# NBP3_Altera_MAX7000_MAX3000_PLCC_Rev1_00.net
KiCad netlist of a schematic drawn in Altium Designer
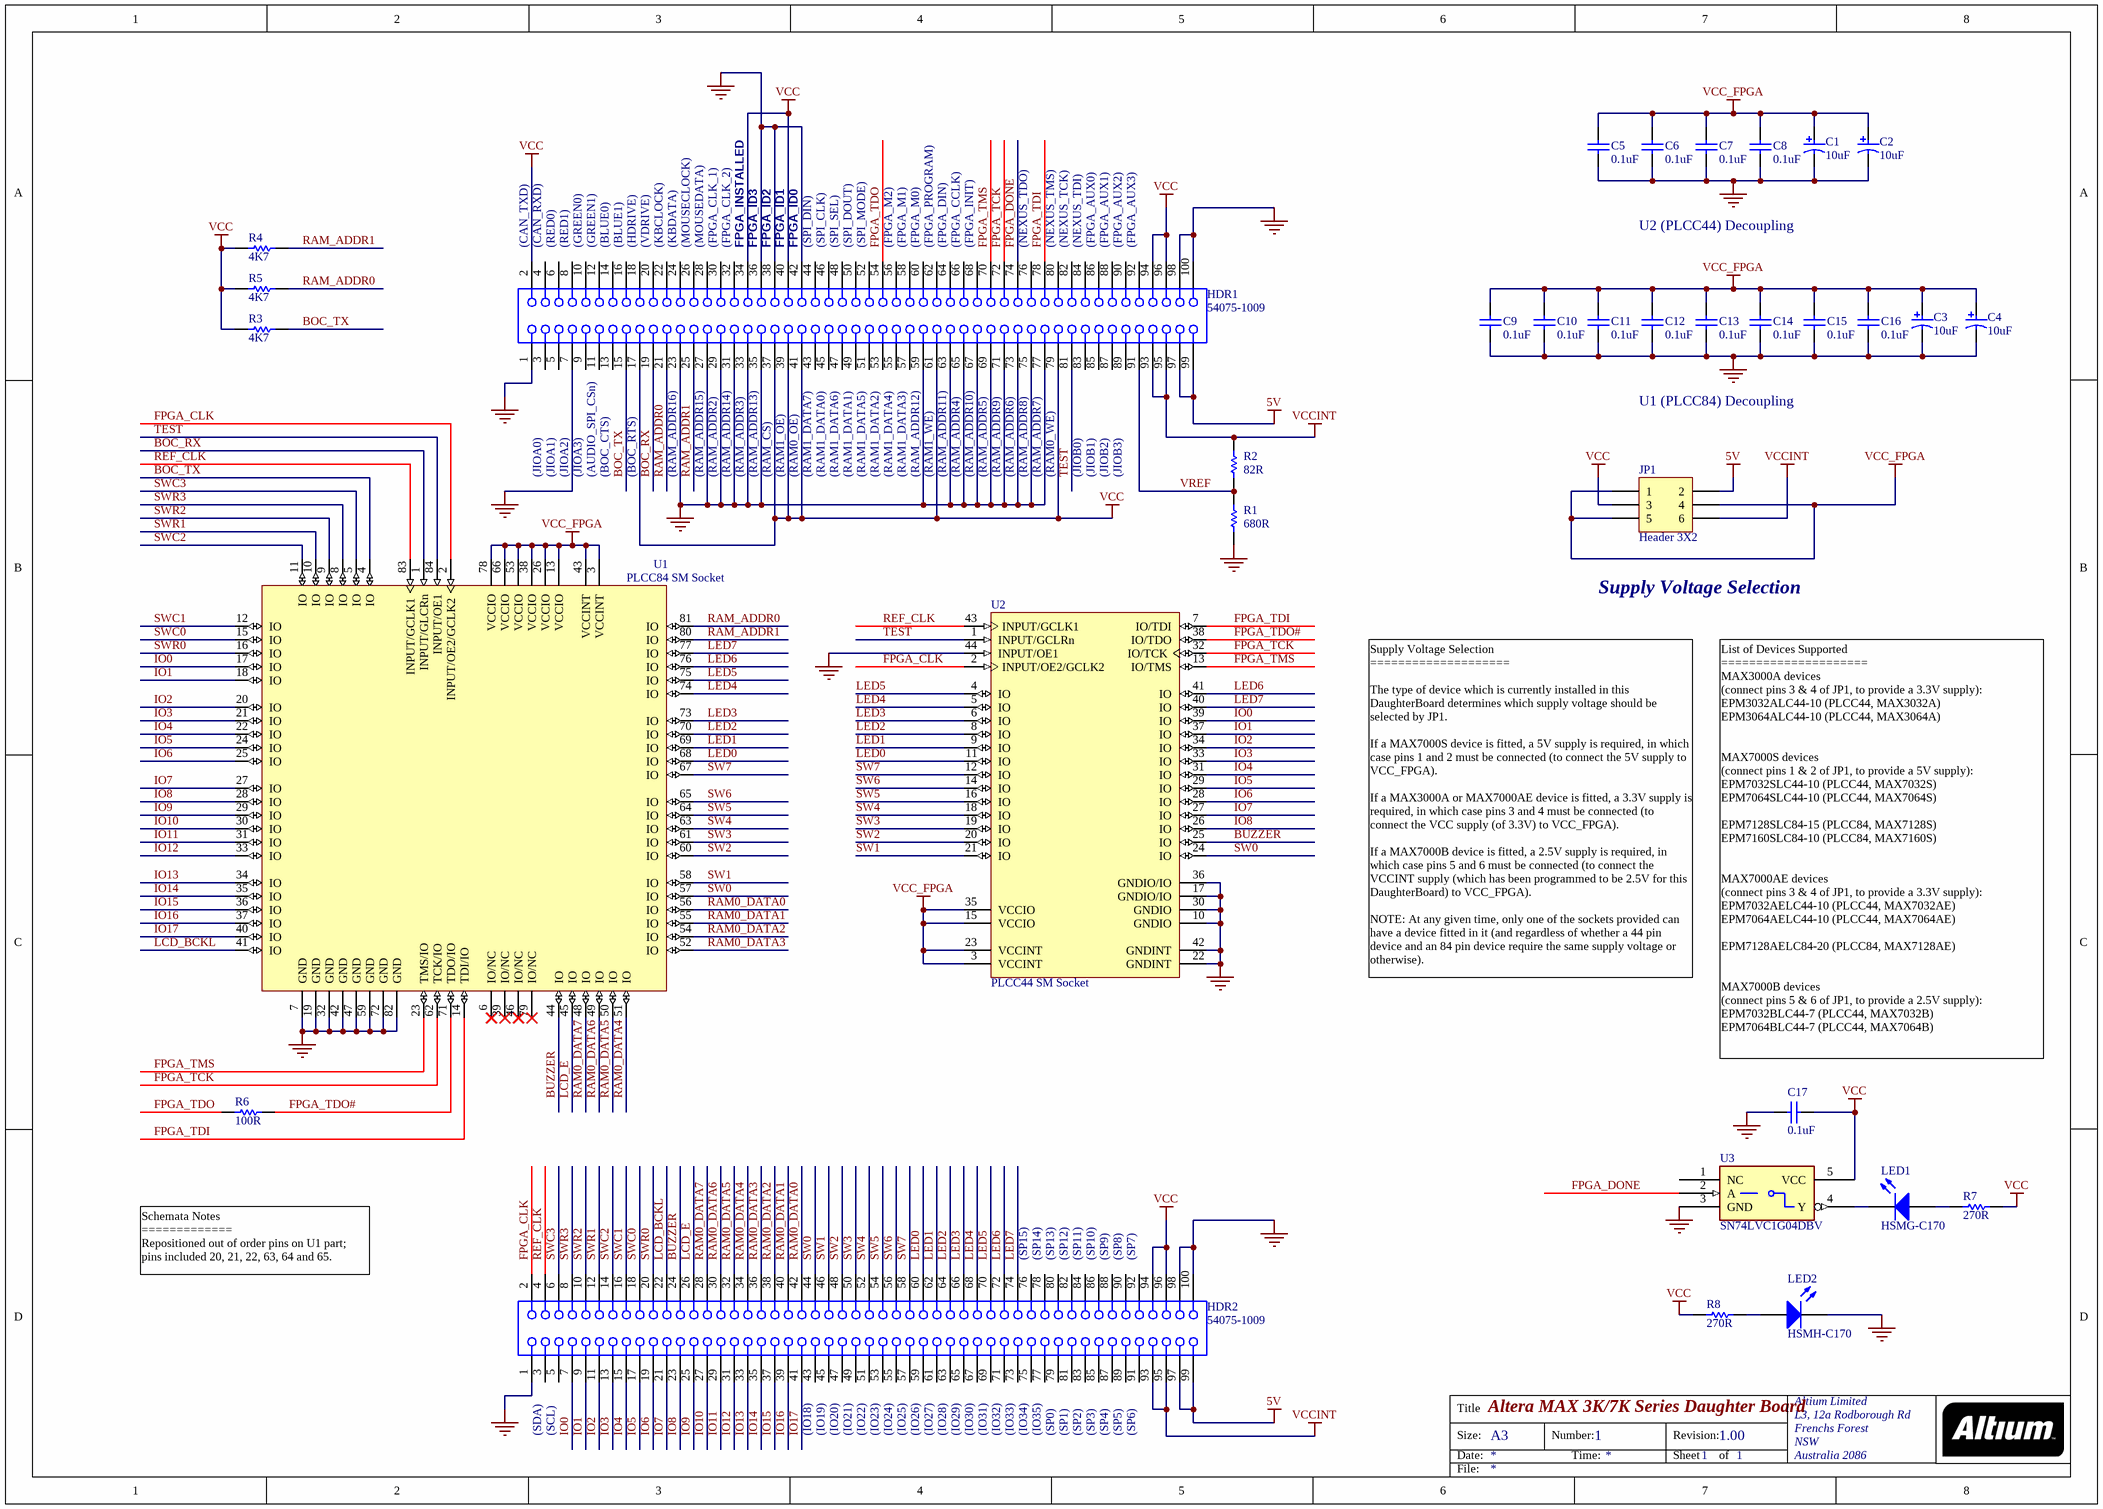
[diagram p0: NBP3 Altera MAX7000 MAX3000 PLCC Rev1.00.SchDoc]

(export (version "E")
  (design (tool "Eeschema 10.0.6"))
  (components
    (comp (ref "C1")
      (value "10uF")
      (footprint "MCCT-B")
      (description "Polar Capacitor")
      (libsource (lib "PassiveSMD") (part "CAP_POLAR"))
    )
    (comp (ref "C2")
      (value "10uF")
      (footprint "MCCT-B")
      (description "Polar Capacitor")
      (libsource (lib "PassiveSMD") (part "CAP_POLAR"))
    )
    (comp (ref "C3")
      (value "10uF")
      (footprint "MCCT-B")
      (description "Polar Capacitor")
      (libsource (lib "PassiveSMD") (part "CAP_POLAR"))
    )
    (comp (ref "C4")
      (value "10uF")
      (footprint "MCCT-B")
      (description "Polar Capacitor")
      (libsource (lib "PassiveSMD") (part "CAP_POLAR"))
    )
    (comp (ref "C5")
      (value "0.1uF")
      (footprint "CC2012-0805")
      (description "Capacitor")
      (libsource (lib "PassiveSMD") (part "CAP"))
    )
    (comp (ref "C6")
      (value "0.1uF")
      (footprint "CC2012-0805")
      (description "Capacitor")
      (libsource (lib "PassiveSMD") (part "CAP"))
    )
    (comp (ref "C7")
      (value "0.1uF")
      (footprint "CC2012-0805")
      (description "Capacitor")
      (libsource (lib "PassiveSMD") (part "CAP"))
    )
    (comp (ref "C8")
      (value "0.1uF")
      (footprint "CC2012-0805")
      (description "Capacitor")
      (libsource (lib "PassiveSMD") (part "CAP"))
    )
    (comp (ref "C9")
      (value "0.1uF")
      (footprint "CC2012-0805")
      (description "Capacitor")
      (libsource (lib "PassiveSMD") (part "CAP"))
    )
    (comp (ref "C10")
      (value "0.1uF")
      (footprint "CC2012-0805")
      (description "Capacitor")
      (libsource (lib "PassiveSMD") (part "CAP"))
    )
    (comp (ref "C11")
      (value "0.1uF")
      (footprint "CC2012-0805")
      (description "Capacitor")
      (libsource (lib "PassiveSMD") (part "CAP"))
    )
    (comp (ref "C12")
      (value "0.1uF")
      (footprint "CC2012-0805")
      (description "Capacitor")
      (libsource (lib "PassiveSMD") (part "CAP"))
    )
    (comp (ref "C13")
      (value "0.1uF")
      (footprint "CC2012-0805")
      (description "Capacitor")
      (libsource (lib "PassiveSMD") (part "CAP"))
    )
    (comp (ref "C14")
      (value "0.1uF")
      (footprint "CC2012-0805")
      (description "Capacitor")
      (libsource (lib "PassiveSMD") (part "CAP"))
    )
    (comp (ref "C15")
      (value "0.1uF")
      (footprint "CC2012-0805")
      (description "Capacitor")
      (libsource (lib "PassiveSMD") (part "CAP"))
    )
    (comp (ref "C16")
      (value "0.1uF")
      (footprint "CC2012-0805")
      (description "Capacitor")
      (libsource (lib "PassiveSMD") (part "CAP"))
    )
    (comp (ref "C17")
      (value "0.1uF")
      (footprint "CC2012-0805")
      (description "Capacitor")
      (libsource (lib "PassiveSMD") (part "CAP"))
    )
    (comp (ref "HDR1")
      (value "54075-1009")
      (footprint "54075")
      (fields
        (field (name "MANUFACTURER") "Molex")
        (field (name "VOLTAGE") "100V")
        (field (name "PUBLISHER") "Altium Limited")
      )
      (libsource (lib "Altium Nanoboard Project") (part "54075-1009"))
    )
    (comp (ref "HDR2")
      (value "54075-1009")
      (footprint "54075")
      (fields
        (field (name "MANUFACTURER") "Molex")
        (field (name "VOLTAGE") "100V")
        (field (name "PUBLISHER") "Altium Limited")
      )
      (libsource (lib "Altium Nanoboard Project") (part "54075-1009"))
    )
    (comp (ref "JP1")
      (value "Header 3X2")
      (footprint "HDR2X3")
      (description "Header, 3-Pin, Dual row")
      (fields (field (name "PUBLISHER") "Altium Limited"))
      (libsource (lib "Miscellaneous Connectors") (part "Header 3X2"))
    )
    (comp (ref "LED1")
      (value "HSMG-C170")
      (footprint "SMD _LED")
      (description "Typical RED GaAs SMD LED Agilent make")
      (fields (field (name "MANUFACTURER") "Generic Components") (field (name "PUBLISHER") "Altium Limited"))
      (libsource (lib "Switches and display") (part "HSMX-C670"))
    )
    (comp (ref "LED2")
      (value "HSMH-C170")
      (footprint "SMD _LED")
      (description "Typical RED GaAs SMD LED Agilent make")
      (fields (field (name "MANUFACTURER") "Generic Components") (field (name "PUBLISHER") "Altium Limited"))
      (libsource (lib "Switches and display") (part "HSMX-C670"))
    )
    (comp (ref "R1")
      (value "680R")
      (footprint "CC2012-0805")
      (description "Resistor")
      (libsource (lib "PassiveSMD") (part "RES"))
    )
    (comp (ref "R2")
      (value "82R")
      (footprint "CC2012-0805")
      (description "Resistor")
      (libsource (lib "PassiveSMD") (part "RES"))
    )
    (comp (ref "R3")
      (value "4K7")
      (footprint "CC2012-0805")
      (description "Resistor")
      (libsource (lib "PassiveSMD") (part "RES"))
    )
    (comp (ref "R4")
      (value "4K7")
      (footprint "CC2012-0805")
      (description "Resistor")
      (libsource (lib "PassiveSMD") (part "RES"))
    )
    (comp (ref "R5")
      (value "4K7")
      (footprint "CC2012-0805")
      (description "Resistor")
      (libsource (lib "PassiveSMD") (part "RES"))
    )
    (comp (ref "R6")
      (value "100R")
      (footprint "CC2012-0805")
      (description "Resistor")
      (libsource (lib "PassiveSMD") (part "RES"))
    )
    (comp (ref "R7")
      (value "270R")
      (footprint "CC2012-0805")
      (description "Resistor")
      (libsource (lib "PassiveSMD") (part "RES"))
    )
    (comp (ref "R8")
      (value "270R")
      (footprint "CC2012-0805")
      (description "Resistor")
      (libsource (lib "PassiveSMD") (part "RES"))
    )
    (comp (ref "U1")
      (value "PLCC84 SM Socket")
      (footprint "PLCC84_SKT_SM")
      (fields (field (name "PUBLISHER") "Altium Limited"))
      (libsource (lib "Altera MAX 7000S") (part "EPM7160SLC84-10"))
    )
    (comp (ref "U2")
      (value "PLCC44 SM Socket")
      (footprint "PLCC44_SKT_SM")
      (description "MAX 3032, 44-Pin PLCC, Speed Grade 10, Commercial Grade")
      (fields (field (name "PUBLISHER") "Altium Limited"))
      (libsource (lib "Altera MAX 3000A") (part "EPM3032ALC44-10"))
    )
    (comp (ref "U3")
      (value "SN74LVC1G04DBV")
      (footprint "SO-G5/P.95")
      (fields (field (name "MANUFACTURER") "TI"))
      (libsource (lib "Philips1GLogic") (part "SN74AHC1G04DBVR"))
    )
  )
  (nets
    (net (code "1") (name "/BOC_RX") (class "Default")
      (node (ref "HDR1") (pin "19") (pinfunction "19_19") (pintype "passive"))
      (node (ref "U1") (pin "1") (pinfunction "INPUT/GLCRn_1") (pintype "input"))
    )
    (net (code "2") (name "/BOC_TX") (class "Default")
      (node (ref "HDR1") (pin "15") (pinfunction "15_15") (pintype "passive"))
      (node (ref "R3") (pin "2") (pinfunction "2_2") (pintype "passive"))
      (node (ref "U1") (pin "4") (pinfunction "IO_4") (pintype "bidirectional"))
    )
    (net (code "3") (name "/BUZZER") (class "Default")
      (node (ref "HDR2") (pin "24") (pinfunction "24_24") (pintype "passive"))
      (node (ref "U1") (pin "44") (pinfunction "IO_44") (pintype "bidirectional"))
      (node (ref "U2") (pin "25") (pinfunction "IO_25") (pintype "bidirectional"))
    )
    (net (code "4") (name "/FPGA_CLK") (class "Default")
      (node (ref "HDR2") (pin "2") (pinfunction "2_2") (pintype "passive"))
      (node (ref "U1") (pin "2") (pinfunction "INPUT/OE2/GCLK2_2") (pintype "input"))
      (node (ref "U2") (pin "2") (pinfunction "INPUT/OE2/GCLK2_2") (pintype "input"))
    )
    (net (code "5") (name "/FPGA_DONE") (class "Default")
      (node (ref "HDR1") (pin "74") (pinfunction "74_74") (pintype "passive"))
      (node (ref "U3") (pin "2") (pinfunction "A_2") (pintype "input"))
    )
    (net (code "6") (name "/FPGA_TCK") (class "Default")
      (node (ref "HDR1") (pin "72") (pinfunction "72_72") (pintype "passive"))
      (node (ref "U1") (pin "62") (pinfunction "TCK/IO_62") (pintype "bidirectional"))
      (node (ref "U2") (pin "32") (pinfunction "IO/TCK_32") (pintype "bidirectional"))
    )
    (net (code "7") (name "/FPGA_TDI") (class "Default")
      (node (ref "HDR1") (pin "78") (pinfunction "78_78") (pintype "passive"))
      (node (ref "U1") (pin "14") (pinfunction "TDI/IO_14") (pintype "bidirectional"))
      (node (ref "U2") (pin "7") (pinfunction "IO/TDI_7") (pintype "bidirectional"))
    )
    (net (code "8") (name "/FPGA_TDO") (class "Default")
      (node (ref "HDR1") (pin "54") (pinfunction "54_54") (pintype "passive"))
      (node (ref "R6") (pin "1") (pinfunction "1_1") (pintype "passive"))
    )
    (net (code "9") (name "/FPGA_TDO#") (class "Default")
      (node (ref "R6") (pin "2") (pinfunction "2_2") (pintype "passive"))
      (node (ref "U1") (pin "71") (pinfunction "TDO/IO_71") (pintype "bidirectional"))
      (node (ref "U2") (pin "38") (pinfunction "IO/TDO_38") (pintype "bidirectional"))
    )
    (net (code "10") (name "/FPGA_TMS") (class "Default")
      (node (ref "HDR1") (pin "70") (pinfunction "70_70") (pintype "passive"))
      (node (ref "U1") (pin "23") (pinfunction "TMS/IO_23") (pintype "bidirectional"))
      (node (ref "U2") (pin "13") (pinfunction "IO/TMS_13") (pintype "bidirectional"))
    )
    (net (code "11") (name "/IO0") (class "Default")
      (node (ref "HDR2") (pin "7") (pinfunction "7_7") (pintype "passive"))
      (node (ref "U1") (pin "17") (pinfunction "IO_17") (pintype "bidirectional"))
      (node (ref "U2") (pin "39") (pinfunction "IO_39") (pintype "bidirectional"))
    )
    (net (code "12") (name "/IO1") (class "Default")
      (node (ref "HDR2") (pin "9") (pinfunction "9_9") (pintype "passive"))
      (node (ref "U1") (pin "18") (pinfunction "IO_18") (pintype "bidirectional"))
      (node (ref "U2") (pin "37") (pinfunction "IO_37") (pintype "bidirectional"))
    )
    (net (code "13") (name "/IO2") (class "Default")
      (node (ref "HDR2") (pin "11") (pinfunction "11_11") (pintype "passive"))
      (node (ref "U1") (pin "20") (pinfunction "IO_20") (pintype "bidirectional"))
      (node (ref "U2") (pin "34") (pinfunction "IO_34") (pintype "bidirectional"))
    )
    (net (code "14") (name "/IO3") (class "Default")
      (node (ref "HDR2") (pin "13") (pinfunction "13_13") (pintype "passive"))
      (node (ref "U1") (pin "21") (pinfunction "IO_21") (pintype "bidirectional"))
      (node (ref "U2") (pin "33") (pinfunction "IO_33") (pintype "bidirectional"))
    )
    (net (code "15") (name "/IO4") (class "Default")
      (node (ref "HDR2") (pin "15") (pinfunction "15_15") (pintype "passive"))
      (node (ref "U1") (pin "22") (pinfunction "IO_22") (pintype "bidirectional"))
      (node (ref "U2") (pin "31") (pinfunction "IO_31") (pintype "bidirectional"))
    )
    (net (code "16") (name "/IO5") (class "Default")
      (node (ref "HDR2") (pin "17") (pinfunction "17_17") (pintype "passive"))
      (node (ref "U1") (pin "24") (pinfunction "IO_24") (pintype "bidirectional"))
      (node (ref "U2") (pin "29") (pinfunction "IO_29") (pintype "bidirectional"))
    )
    (net (code "17") (name "/IO6") (class "Default")
      (node (ref "HDR2") (pin "19") (pinfunction "19_19") (pintype "passive"))
      (node (ref "U1") (pin "25") (pinfunction "IO_25") (pintype "bidirectional"))
      (node (ref "U2") (pin "28") (pinfunction "IO_28") (pintype "bidirectional"))
    )
    (net (code "18") (name "/IO7") (class "Default")
      (node (ref "HDR2") (pin "21") (pinfunction "21_21") (pintype "passive"))
      (node (ref "U1") (pin "27") (pinfunction "IO_27") (pintype "bidirectional"))
      (node (ref "U2") (pin "27") (pinfunction "IO_27") (pintype "bidirectional"))
    )
    (net (code "19") (name "/IO8") (class "Default")
      (node (ref "HDR2") (pin "23") (pinfunction "23_23") (pintype "passive"))
      (node (ref "U1") (pin "28") (pinfunction "IO_28") (pintype "bidirectional"))
      (node (ref "U2") (pin "26") (pinfunction "IO_26") (pintype "bidirectional"))
    )
    (net (code "20") (name "/IO9") (class "Default")
      (node (ref "HDR2") (pin "25") (pinfunction "25_25") (pintype "passive"))
      (node (ref "U1") (pin "29") (pinfunction "IO_29") (pintype "bidirectional"))
    )
    (net (code "21") (name "/IO10") (class "Default")
      (node (ref "HDR2") (pin "27") (pinfunction "27_27") (pintype "passive"))
      (node (ref "U1") (pin "30") (pinfunction "IO_30") (pintype "bidirectional"))
    )
    (net (code "22") (name "/IO11") (class "Default")
      (node (ref "HDR2") (pin "29") (pinfunction "29_29") (pintype "passive"))
      (node (ref "U1") (pin "31") (pinfunction "IO_31") (pintype "bidirectional"))
    )
    (net (code "23") (name "/IO12") (class "Default")
      (node (ref "HDR2") (pin "31") (pinfunction "31_31") (pintype "passive"))
      (node (ref "U1") (pin "33") (pinfunction "IO_33") (pintype "bidirectional"))
    )
    (net (code "24") (name "/IO13") (class "Default")
      (node (ref "HDR2") (pin "33") (pinfunction "33_33") (pintype "passive"))
      (node (ref "U1") (pin "34") (pinfunction "IO_34") (pintype "bidirectional"))
    )
    (net (code "25") (name "/IO14") (class "Default")
      (node (ref "HDR2") (pin "35") (pinfunction "35_35") (pintype "passive"))
      (node (ref "U1") (pin "35") (pinfunction "IO_35") (pintype "bidirectional"))
    )
    (net (code "26") (name "/IO15") (class "Default")
      (node (ref "HDR2") (pin "37") (pinfunction "37_37") (pintype "passive"))
      (node (ref "U1") (pin "36") (pinfunction "IO_36") (pintype "bidirectional"))
    )
    (net (code "27") (name "/IO16") (class "Default")
      (node (ref "HDR2") (pin "39") (pinfunction "39_39") (pintype "passive"))
      (node (ref "U1") (pin "37") (pinfunction "IO_37") (pintype "bidirectional"))
    )
    (net (code "28") (name "/IO17") (class "Default")
      (node (ref "HDR2") (pin "41") (pinfunction "41_41") (pintype "passive"))
      (node (ref "U1") (pin "40") (pinfunction "IO_40") (pintype "bidirectional"))
    )
    (net (code "29") (name "/LCD_BCKL") (class "Default")
      (node (ref "HDR2") (pin "22") (pinfunction "22_22") (pintype "passive"))
      (node (ref "U1") (pin "41") (pinfunction "IO_41") (pintype "bidirectional"))
    )
    (net (code "30") (name "/LCD_E") (class "Default")
      (node (ref "HDR2") (pin "26") (pinfunction "26_26") (pintype "passive"))
      (node (ref "U1") (pin "45") (pinfunction "IO_45") (pintype "bidirectional"))
    )
    (net (code "31") (name "/LED0") (class "Default")
      (node (ref "HDR2") (pin "60") (pinfunction "60_60") (pintype "passive"))
      (node (ref "U1") (pin "68") (pinfunction "IO_68") (pintype "bidirectional"))
      (node (ref "U2") (pin "11") (pinfunction "IO_11") (pintype "bidirectional"))
    )
    (net (code "32") (name "/LED1") (class "Default")
      (node (ref "HDR2") (pin "62") (pinfunction "62_62") (pintype "passive"))
      (node (ref "U1") (pin "69") (pinfunction "IO_69") (pintype "bidirectional"))
      (node (ref "U2") (pin "9") (pinfunction "IO_9") (pintype "bidirectional"))
    )
    (net (code "33") (name "/LED2") (class "Default")
      (node (ref "HDR2") (pin "64") (pinfunction "64_64") (pintype "passive"))
      (node (ref "U1") (pin "70") (pinfunction "IO_70") (pintype "bidirectional"))
      (node (ref "U2") (pin "8") (pinfunction "IO_8") (pintype "bidirectional"))
    )
    (net (code "34") (name "/LED3") (class "Default")
      (node (ref "HDR2") (pin "66") (pinfunction "66_66") (pintype "passive"))
      (node (ref "U1") (pin "73") (pinfunction "IO_73") (pintype "bidirectional"))
      (node (ref "U2") (pin "6") (pinfunction "IO_6") (pintype "bidirectional"))
    )
    (net (code "35") (name "/LED4") (class "Default")
      (node (ref "HDR2") (pin "68") (pinfunction "68_68") (pintype "passive"))
      (node (ref "U1") (pin "74") (pinfunction "IO_74") (pintype "bidirectional"))
      (node (ref "U2") (pin "5") (pinfunction "IO_5") (pintype "bidirectional"))
    )
    (net (code "36") (name "/LED5") (class "Default")
      (node (ref "HDR2") (pin "70") (pinfunction "70_70") (pintype "passive"))
      (node (ref "U1") (pin "75") (pinfunction "IO_75") (pintype "bidirectional"))
      (node (ref "U2") (pin "4") (pinfunction "IO_4") (pintype "bidirectional"))
    )
    (net (code "37") (name "/LED6") (class "Default")
      (node (ref "HDR2") (pin "72") (pinfunction "72_72") (pintype "passive"))
      (node (ref "U1") (pin "76") (pinfunction "IO_76") (pintype "bidirectional"))
      (node (ref "U2") (pin "41") (pinfunction "IO_41") (pintype "bidirectional"))
    )
    (net (code "38") (name "/LED7") (class "Default")
      (node (ref "HDR2") (pin "74") (pinfunction "74_74") (pintype "passive"))
      (node (ref "U1") (pin "77") (pinfunction "IO_77") (pintype "bidirectional"))
      (node (ref "U2") (pin "40") (pinfunction "IO_40") (pintype "bidirectional"))
    )
    (net (code "39") (name "/RAM0_DATA0") (class "Default")
      (node (ref "HDR2") (pin "42") (pinfunction "42_42") (pintype "passive"))
      (node (ref "U1") (pin "56") (pinfunction "IO_56") (pintype "bidirectional"))
    )
    (net (code "40") (name "/RAM0_DATA1") (class "Default")
      (node (ref "HDR2") (pin "40") (pinfunction "40_40") (pintype "passive"))
      (node (ref "U1") (pin "55") (pinfunction "IO_55") (pintype "bidirectional"))
    )
    (net (code "41") (name "/RAM0_DATA2") (class "Default")
      (node (ref "HDR2") (pin "38") (pinfunction "38_38") (pintype "passive"))
      (node (ref "U1") (pin "54") (pinfunction "IO_54") (pintype "bidirectional"))
    )
    (net (code "42") (name "/RAM0_DATA3") (class "Default")
      (node (ref "HDR2") (pin "36") (pinfunction "36_36") (pintype "passive"))
      (node (ref "U1") (pin "52") (pinfunction "IO_52") (pintype "bidirectional"))
    )
    (net (code "43") (name "/RAM0_DATA4") (class "Default")
      (node (ref "HDR2") (pin "34") (pinfunction "34_34") (pintype "passive"))
      (node (ref "U1") (pin "51") (pinfunction "IO_51") (pintype "bidirectional"))
    )
    (net (code "44") (name "/RAM0_DATA5") (class "Default")
      (node (ref "HDR2") (pin "32") (pinfunction "32_32") (pintype "passive"))
      (node (ref "U1") (pin "50") (pinfunction "IO_50") (pintype "bidirectional"))
    )
    (net (code "45") (name "/RAM0_DATA6") (class "Default")
      (node (ref "HDR2") (pin "30") (pinfunction "30_30") (pintype "passive"))
      (node (ref "U1") (pin "49") (pinfunction "IO_49") (pintype "bidirectional"))
    )
    (net (code "46") (name "/RAM0_DATA7") (class "Default")
      (node (ref "HDR2") (pin "28") (pinfunction "28_28") (pintype "passive"))
      (node (ref "U1") (pin "48") (pinfunction "IO_48") (pintype "bidirectional"))
    )
    (net (code "47") (name "/RAM_ADDR0") (class "Default")
      (node (ref "HDR1") (pin "21") (pinfunction "21_21") (pintype "passive"))
      (node (ref "R5") (pin "2") (pinfunction "2_2") (pintype "passive"))
      (node (ref "U1") (pin "81") (pinfunction "IO_81") (pintype "bidirectional"))
    )
    (net (code "48") (name "/RAM_ADDR1") (class "Default")
      (node (ref "HDR1") (pin "25") (pinfunction "25_25") (pintype "passive"))
      (node (ref "R4") (pin "2") (pinfunction "2_2") (pintype "passive"))
      (node (ref "U1") (pin "80") (pinfunction "IO_80") (pintype "bidirectional"))
    )
    (net (code "49") (name "/REF_CLK") (class "Default")
      (node (ref "HDR2") (pin "4") (pinfunction "4_4") (pintype "passive"))
      (node (ref "U1") (pin "83") (pinfunction "INPUT/GCLK1_83") (pintype "input"))
      (node (ref "U2") (pin "43") (pinfunction "INPUT/GCLK1_43") (pintype "input"))
    )
    (net (code "50") (name "/SW0") (class "Default")
      (node (ref "HDR2") (pin "44") (pinfunction "44_44") (pintype "passive"))
      (node (ref "U1") (pin "57") (pinfunction "IO_57") (pintype "bidirectional"))
      (node (ref "U2") (pin "24") (pinfunction "IO_24") (pintype "bidirectional"))
    )
    (net (code "51") (name "/SW1") (class "Default")
      (node (ref "HDR2") (pin "46") (pinfunction "46_46") (pintype "passive"))
      (node (ref "U1") (pin "58") (pinfunction "IO_58") (pintype "bidirectional"))
      (node (ref "U2") (pin "21") (pinfunction "IO_21") (pintype "bidirectional"))
    )
    (net (code "52") (name "/SW2") (class "Default")
      (node (ref "HDR2") (pin "48") (pinfunction "48_48") (pintype "passive"))
      (node (ref "U1") (pin "60") (pinfunction "IO_60") (pintype "bidirectional"))
      (node (ref "U2") (pin "20") (pinfunction "IO_20") (pintype "bidirectional"))
    )
    (net (code "53") (name "/SW3") (class "Default")
      (node (ref "HDR2") (pin "50") (pinfunction "50_50") (pintype "passive"))
      (node (ref "U1") (pin "61") (pinfunction "IO_61") (pintype "bidirectional"))
      (node (ref "U2") (pin "19") (pinfunction "IO_19") (pintype "bidirectional"))
    )
    (net (code "54") (name "/SW4") (class "Default")
      (node (ref "HDR2") (pin "52") (pinfunction "52_52") (pintype "passive"))
      (node (ref "U1") (pin "63") (pinfunction "IO_63") (pintype "bidirectional"))
      (node (ref "U2") (pin "18") (pinfunction "IO_18") (pintype "bidirectional"))
    )
    (net (code "55") (name "/SW5") (class "Default")
      (node (ref "HDR2") (pin "54") (pinfunction "54_54") (pintype "passive"))
      (node (ref "U1") (pin "64") (pinfunction "IO_64") (pintype "bidirectional"))
      (node (ref "U2") (pin "16") (pinfunction "IO_16") (pintype "bidirectional"))
    )
    (net (code "56") (name "/SW6") (class "Default")
      (node (ref "HDR2") (pin "56") (pinfunction "56_56") (pintype "passive"))
      (node (ref "U1") (pin "65") (pinfunction "IO_65") (pintype "bidirectional"))
      (node (ref "U2") (pin "14") (pinfunction "IO_14") (pintype "bidirectional"))
    )
    (net (code "57") (name "/SW7") (class "Default")
      (node (ref "HDR2") (pin "58") (pinfunction "58_58") (pintype "passive"))
      (node (ref "U1") (pin "67") (pinfunction "IO_67") (pintype "bidirectional"))
      (node (ref "U2") (pin "12") (pinfunction "IO_12") (pintype "bidirectional"))
    )
    (net (code "58") (name "/SWC0") (class "Default")
      (node (ref "HDR2") (pin "18") (pinfunction "18_18") (pintype "passive"))
      (node (ref "U1") (pin "15") (pinfunction "IO_15") (pintype "bidirectional"))
    )
    (net (code "59") (name "/SWC1") (class "Default")
      (node (ref "HDR2") (pin "16") (pinfunction "16_16") (pintype "passive"))
      (node (ref "U1") (pin "12") (pinfunction "IO_12") (pintype "bidirectional"))
    )
    (net (code "60") (name "/SWC2") (class "Default")
      (node (ref "HDR2") (pin "14") (pinfunction "14_14") (pintype "passive"))
      (node (ref "U1") (pin "11") (pinfunction "IO_11") (pintype "bidirectional"))
    )
    (net (code "61") (name "/SWC3") (class "Default")
      (node (ref "HDR2") (pin "6") (pinfunction "6_6") (pintype "passive"))
      (node (ref "U1") (pin "5") (pinfunction "IO_5") (pintype "bidirectional"))
    )
    (net (code "62") (name "/SWR0") (class "Default")
      (node (ref "HDR2") (pin "20") (pinfunction "20_20") (pintype "passive"))
      (node (ref "U1") (pin "16") (pinfunction "IO_16") (pintype "bidirectional"))
    )
    (net (code "63") (name "/SWR1") (class "Default")
      (node (ref "HDR2") (pin "12") (pinfunction "12_12") (pintype "passive"))
      (node (ref "U1") (pin "10") (pinfunction "IO_10") (pintype "bidirectional"))
    )
    (net (code "64") (name "/SWR2") (class "Default")
      (node (ref "HDR2") (pin "10") (pinfunction "10_10") (pintype "passive"))
      (node (ref "U1") (pin "9") (pinfunction "IO_9") (pintype "bidirectional"))
    )
    (net (code "65") (name "/SWR3") (class "Default")
      (node (ref "HDR2") (pin "8") (pinfunction "8_8") (pintype "passive"))
      (node (ref "U1") (pin "8") (pinfunction "IO_8") (pintype "bidirectional"))
    )
    (net (code "66") (name "/TEST") (class "Default")
      (node (ref "HDR1") (pin "81") (pinfunction "81_81") (pintype "passive"))
      (node (ref "U1") (pin "84") (pinfunction "INPUT/OE1_84") (pintype "input"))
      (node (ref "U2") (pin "1") (pinfunction "INPUT/GCLRn_1") (pintype "input"))
    )
    (net (code "67") (name "/VREF") (class "Default")
      (node (ref "HDR1") (pin "91") (pinfunction "91_91") (pintype "passive"))
      (node (ref "R1") (pin "1") (pinfunction "1_1") (pintype "passive"))
      (node (ref "R2") (pin "2") (pinfunction "2_2") (pintype "passive"))
    )
    (net (code "68") (name "5V") (class "Default")
      (node (ref "HDR1") (pin "97") (pinfunction "97_97") (pintype "passive"))
      (node (ref "HDR1") (pin "99") (pinfunction "99_99") (pintype "passive"))
      (node (ref "HDR2") (pin "97") (pinfunction "97_97") (pintype "passive"))
      (node (ref "HDR2") (pin "99") (pinfunction "99_99") (pintype "passive"))
      (node (ref "JP1") (pin "2") (pinfunction "2_2") (pintype "passive"))
    )
    (net (code "69") (name "GND") (class "Default")
      (node (ref "C1") (pin "2") (pinfunction "2_2") (pintype "passive"))
      (node (ref "C10") (pin "1") (pinfunction "1_1") (pintype "passive"))
      (node (ref "C11") (pin "1") (pinfunction "1_1") (pintype "passive"))
      (node (ref "C12") (pin "2") (pinfunction "2_2") (pintype "passive"))
      (node (ref "C13") (pin "1") (pinfunction "1_1") (pintype "passive"))
      (node (ref "C14") (pin "2") (pinfunction "2_2") (pintype "passive"))
      (node (ref "C15") (pin "2") (pinfunction "2_2") (pintype "passive"))
      (node (ref "C16") (pin "2") (pinfunction "2_2") (pintype "passive"))
      (node (ref "C17") (pin "2") (pinfunction "2_2") (pintype "passive"))
      (node (ref "C2") (pin "2") (pinfunction "2_2") (pintype "passive"))
      (node (ref "C3") (pin "2") (pinfunction "2_2") (pintype "passive"))
      (node (ref "C4") (pin "2") (pinfunction "2_2") (pintype "passive"))
      (node (ref "C5") (pin "2") (pinfunction "2_2") (pintype "passive"))
      (node (ref "C6") (pin "2") (pinfunction "2_2") (pintype "passive"))
      (node (ref "C7") (pin "2") (pinfunction "2_2") (pintype "passive"))
      (node (ref "C8") (pin "2") (pinfunction "2_2") (pintype "passive"))
      (node (ref "C9") (pin "1") (pinfunction "1_1") (pintype "passive"))
      (node (ref "HDR1") (pin "1") (pinfunction "1_1") (pintype "passive"))
      (node (ref "HDR1") (pin "100") (pinfunction "100_100") (pintype "passive"))
      (node (ref "HDR1") (pin "23") (pinfunction "23_23") (pintype "passive"))
      (node (ref "HDR1") (pin "27") (pinfunction "27_27") (pintype "passive"))
      (node (ref "HDR1") (pin "29") (pinfunction "29_29") (pintype "passive"))
      (node (ref "HDR1") (pin "31") (pinfunction "31_31") (pintype "passive"))
      (node (ref "HDR1") (pin "33") (pinfunction "33_33") (pintype "passive"))
      (node (ref "HDR1") (pin "35") (pinfunction "35_35") (pintype "passive"))
      (node (ref "HDR1") (pin "36") (pinfunction "36_36") (pintype "passive"))
      (node (ref "HDR1") (pin "38") (pinfunction "38_38") (pintype "passive"))
      (node (ref "HDR1") (pin "42") (pinfunction "42_42") (pintype "passive"))
      (node (ref "HDR1") (pin "59") (pinfunction "59_59") (pintype "passive"))
      (node (ref "HDR1") (pin "63") (pinfunction "63_63") (pintype "passive"))
      (node (ref "HDR1") (pin "65") (pinfunction "65_65") (pintype "passive"))
      (node (ref "HDR1") (pin "67") (pinfunction "67_67") (pintype "passive"))
      (node (ref "HDR1") (pin "69") (pinfunction "69_69") (pintype "passive"))
      (node (ref "HDR1") (pin "7") (pinfunction "7_7") (pintype "passive"))
      (node (ref "HDR1") (pin "71") (pinfunction "71_71") (pintype "passive"))
      (node (ref "HDR1") (pin "73") (pinfunction "73_73") (pintype "passive"))
      (node (ref "HDR1") (pin "75") (pinfunction "75_75") (pintype "passive"))
      (node (ref "HDR1") (pin "77") (pinfunction "77_77") (pintype "passive"))
      (node (ref "HDR1") (pin "98") (pinfunction "98_98") (pintype "passive"))
      (node (ref "HDR2") (pin "1") (pinfunction "1_1") (pintype "passive"))
      (node (ref "HDR2") (pin "100") (pinfunction "100_100") (pintype "passive"))
      (node (ref "HDR2") (pin "98") (pinfunction "98_98") (pintype "passive"))
      (node (ref "LED2") (pin "2") (pinfunction "K_2") (pintype "passive"))
      (node (ref "R1") (pin "2") (pinfunction "2_2") (pintype "passive"))
      (node (ref "U1") (pin "19") (pinfunction "GND_19") (pintype "power_in"))
      (node (ref "U1") (pin "32") (pinfunction "GND_32") (pintype "power_in"))
      (node (ref "U1") (pin "42") (pinfunction "GND_42") (pintype "power_in"))
      (node (ref "U1") (pin "47") (pinfunction "GND_47") (pintype "power_in"))
      (node (ref "U1") (pin "59") (pinfunction "GND_59") (pintype "power_in"))
      (node (ref "U1") (pin "7") (pinfunction "GND_7") (pintype "power_in"))
      (node (ref "U1") (pin "72") (pinfunction "GND_72") (pintype "power_in"))
      (node (ref "U1") (pin "82") (pinfunction "GND_82") (pintype "power_in"))
      (node (ref "U2") (pin "10") (pinfunction "GNDIO_10") (pintype "power_in"))
      (node (ref "U2") (pin "17") (pinfunction "GNDIO/IO_17") (pintype "power_in"))
      (node (ref "U2") (pin "22") (pinfunction "GNDINT_22") (pintype "power_in"))
      (node (ref "U2") (pin "30") (pinfunction "GNDIO_30") (pintype "power_in"))
      (node (ref "U2") (pin "36") (pinfunction "GNDIO/IO_36") (pintype "power_in"))
      (node (ref "U2") (pin "42") (pinfunction "GNDINT_42") (pintype "power_in"))
      (node (ref "U2") (pin "44") (pinfunction "INPUT/OE1_44") (pintype "input"))
      (node (ref "U3") (pin "3") (pinfunction "GND_3") (pintype "power_in"))
    )
    (net (code "70") (name "Net-(LED1-A)") (class "Default")
      (node (ref "LED1") (pin "1") (pinfunction "A_1") (pintype "passive"))
      (node (ref "R7") (pin "2") (pinfunction "2_2") (pintype "passive"))
    )
    (net (code "71") (name "Net-(LED1-K)") (class "Default")
      (node (ref "LED1") (pin "2") (pinfunction "K_2") (pintype "passive"))
      (node (ref "U3") (pin "4") (pinfunction "Y_4") (pintype "output"))
    )
    (net (code "72") (name "Net-(LED2-A)") (class "Default")
      (node (ref "LED2") (pin "1") (pinfunction "A_1") (pintype "passive"))
      (node (ref "R8") (pin "2") (pinfunction "2_2") (pintype "passive"))
    )
    (net (code "73") (name "VCC") (class "Default")
      (node (ref "C17") (pin "1") (pinfunction "1_1") (pintype "passive"))
      (node (ref "HDR1") (pin "17") (pinfunction "17_17") (pintype "passive"))
      (node (ref "HDR1") (pin "2") (pinfunction "2_2") (pintype "passive"))
      (node (ref "HDR1") (pin "34") (pinfunction "34_34") (pintype "passive"))
      (node (ref "HDR1") (pin "37") (pinfunction "37_37") (pintype "passive"))
      (node (ref "HDR1") (pin "39") (pinfunction "39_39") (pintype "passive"))
      (node (ref "HDR1") (pin "40") (pinfunction "40_40") (pintype "passive"))
      (node (ref "HDR1") (pin "41") (pinfunction "41_41") (pintype "passive"))
      (node (ref "HDR1") (pin "61") (pinfunction "61_61") (pintype "passive"))
      (node (ref "HDR1") (pin "79") (pinfunction "79_79") (pintype "passive"))
      (node (ref "HDR1") (pin "94") (pinfunction "94_94") (pintype "passive"))
      (node (ref "HDR1") (pin "96") (pinfunction "96_96") (pintype "passive"))
      (node (ref "HDR2") (pin "94") (pinfunction "94_94") (pintype "passive"))
      (node (ref "HDR2") (pin "96") (pinfunction "96_96") (pintype "passive"))
      (node (ref "JP1") (pin "3") (pinfunction "3_3") (pintype "passive"))
      (node (ref "R3") (pin "1") (pinfunction "1_1") (pintype "passive"))
      (node (ref "R4") (pin "1") (pinfunction "1_1") (pintype "passive"))
      (node (ref "R5") (pin "1") (pinfunction "1_1") (pintype "passive"))
      (node (ref "R7") (pin "1") (pinfunction "1_1") (pintype "passive"))
      (node (ref "R8") (pin "1") (pinfunction "1_1") (pintype "passive"))
      (node (ref "U3") (pin "5") (pinfunction "VCC_5") (pintype "power_in"))
    )
    (net (code "74") (name "VCCINT") (class "Default")
      (node (ref "HDR1") (pin "93") (pinfunction "93_93") (pintype "passive"))
      (node (ref "HDR1") (pin "95") (pinfunction "95_95") (pintype "passive"))
      (node (ref "HDR2") (pin "93") (pinfunction "93_93") (pintype "passive"))
      (node (ref "HDR2") (pin "95") (pinfunction "95_95") (pintype "passive"))
      (node (ref "JP1") (pin "6") (pinfunction "6_6") (pintype "passive"))
      (node (ref "R2") (pin "1") (pinfunction "1_1") (pintype "passive"))
    )
    (net (code "75") (name "VCC_FPGA") (class "Default")
      (node (ref "C1") (pin "1") (pinfunction "1_1") (pintype "passive"))
      (node (ref "C10") (pin "2") (pinfunction "2_2") (pintype "passive"))
      (node (ref "C11") (pin "2") (pinfunction "2_2") (pintype "passive"))
      (node (ref "C12") (pin "1") (pinfunction "1_1") (pintype "passive"))
      (node (ref "C13") (pin "2") (pinfunction "2_2") (pintype "passive"))
      (node (ref "C14") (pin "1") (pinfunction "1_1") (pintype "passive"))
      (node (ref "C15") (pin "1") (pinfunction "1_1") (pintype "passive"))
      (node (ref "C16") (pin "1") (pinfunction "1_1") (pintype "passive"))
      (node (ref "C2") (pin "1") (pinfunction "1_1") (pintype "passive"))
      (node (ref "C3") (pin "1") (pinfunction "1_1") (pintype "passive"))
      (node (ref "C4") (pin "1") (pinfunction "1_1") (pintype "passive"))
      (node (ref "C5") (pin "1") (pinfunction "1_1") (pintype "passive"))
      (node (ref "C6") (pin "1") (pinfunction "1_1") (pintype "passive"))
      (node (ref "C7") (pin "1") (pinfunction "1_1") (pintype "passive"))
      (node (ref "C8") (pin "1") (pinfunction "1_1") (pintype "passive"))
      (node (ref "C9") (pin "2") (pinfunction "2_2") (pintype "passive"))
      (node (ref "JP1") (pin "1") (pinfunction "1_1") (pintype "passive"))
      (node (ref "JP1") (pin "4") (pinfunction "4_4") (pintype "passive"))
      (node (ref "JP1") (pin "5") (pinfunction "5_5") (pintype "passive"))
      (node (ref "U1") (pin "13") (pinfunction "VCCIO_13") (pintype "power_in"))
      (node (ref "U1") (pin "26") (pinfunction "VCCIO_26") (pintype "power_in"))
      (node (ref "U1") (pin "3") (pinfunction "VCCINT_3") (pintype "power_in"))
      (node (ref "U1") (pin "38") (pinfunction "VCCIO_38") (pintype "power_in"))
      (node (ref "U1") (pin "43") (pinfunction "VCCINT_43") (pintype "power_in"))
      (node (ref "U1") (pin "53") (pinfunction "VCCIO_53") (pintype "power_in"))
      (node (ref "U1") (pin "66") (pinfunction "VCCIO_66") (pintype "power_in"))
      (node (ref "U1") (pin "78") (pinfunction "VCCIO_78") (pintype "power_in"))
      (node (ref "U2") (pin "15") (pinfunction "VCCIO_15") (pintype "power_in"))
      (node (ref "U2") (pin "23") (pinfunction "VCCINT_23") (pintype "power_in"))
      (node (ref "U2") (pin "3") (pinfunction "VCCINT_3") (pintype "power_in"))
      (node (ref "U2") (pin "35") (pinfunction "VCCIO_35") (pintype "power_in"))
    )
    (net (code "76") (name "unconnected-(HDR1-Pad3)") (class "Default")
      (node (ref "HDR1") (pin "3") (pinfunction "3_3") (pintype "passive"))
    )
    (net (code "77") (name "unconnected-(HDR1-Pad4)") (class "Default")
      (node (ref "HDR1") (pin "4") (pinfunction "4_4") (pintype "passive"))
    )
    (net (code "78") (name "unconnected-(HDR1-Pad5)") (class "Default")
      (node (ref "HDR1") (pin "5") (pinfunction "5_5") (pintype "passive"))
    )
    (net (code "79") (name "unconnected-(HDR1-Pad6)") (class "Default")
      (node (ref "HDR1") (pin "6") (pinfunction "6_6") (pintype "passive"))
    )
    (net (code "80") (name "unconnected-(HDR1-Pad8)") (class "Default")
      (node (ref "HDR1") (pin "8") (pinfunction "8_8") (pintype "passive"))
    )
    (net (code "81") (name "unconnected-(HDR1-Pad9)") (class "Default")
      (node (ref "HDR1") (pin "9") (pinfunction "9_9") (pintype "passive"))
    )
    (net (code "82") (name "unconnected-(HDR1-Pad10)") (class "Default")
      (node (ref "HDR1") (pin "10") (pinfunction "10_10") (pintype "passive"))
    )
    (net (code "83") (name "unconnected-(HDR1-Pad11)") (class "Default")
      (node (ref "HDR1") (pin "11") (pinfunction "11_11") (pintype "passive"))
    )
    (net (code "84") (name "unconnected-(HDR1-Pad12)") (class "Default")
      (node (ref "HDR1") (pin "12") (pinfunction "12_12") (pintype "passive"))
    )
    (net (code "85") (name "unconnected-(HDR1-Pad13)") (class "Default")
      (node (ref "HDR1") (pin "13") (pinfunction "13_13") (pintype "passive"))
    )
    (net (code "86") (name "unconnected-(HDR1-Pad14)") (class "Default")
      (node (ref "HDR1") (pin "14") (pinfunction "14_14") (pintype "passive"))
    )
    (net (code "87") (name "unconnected-(HDR1-Pad16)") (class "Default")
      (node (ref "HDR1") (pin "16") (pinfunction "16_16") (pintype "passive"))
    )
    (net (code "88") (name "unconnected-(HDR1-Pad18)") (class "Default")
      (node (ref "HDR1") (pin "18") (pinfunction "18_18") (pintype "passive"))
    )
    (net (code "89") (name "unconnected-(HDR1-Pad20)") (class "Default")
      (node (ref "HDR1") (pin "20") (pinfunction "20_20") (pintype "passive"))
    )
    (net (code "90") (name "unconnected-(HDR1-Pad22)") (class "Default")
      (node (ref "HDR1") (pin "22") (pinfunction "22_22") (pintype "passive"))
    )
    (net (code "91") (name "unconnected-(HDR1-Pad24)") (class "Default")
      (node (ref "HDR1") (pin "24") (pinfunction "24_24") (pintype "passive"))
    )
    (net (code "92") (name "unconnected-(HDR1-Pad26)") (class "Default")
      (node (ref "HDR1") (pin "26") (pinfunction "26_26") (pintype "passive"))
    )
    (net (code "93") (name "unconnected-(HDR1-Pad28)") (class "Default")
      (node (ref "HDR1") (pin "28") (pinfunction "28_28") (pintype "passive"))
    )
    (net (code "94") (name "unconnected-(HDR1-Pad30)") (class "Default")
      (node (ref "HDR1") (pin "30") (pinfunction "30_30") (pintype "passive"))
    )
    (net (code "95") (name "unconnected-(HDR1-Pad32)") (class "Default")
      (node (ref "HDR1") (pin "32") (pinfunction "32_32") (pintype "passive"))
    )
    (net (code "96") (name "unconnected-(HDR1-Pad43)") (class "Default")
      (node (ref "HDR1") (pin "43") (pinfunction "43_43") (pintype "passive"))
    )
    (net (code "97") (name "unconnected-(HDR1-Pad44)") (class "Default")
      (node (ref "HDR1") (pin "44") (pinfunction "44_44") (pintype "passive"))
    )
    (net (code "98") (name "unconnected-(HDR1-Pad45)") (class "Default")
      (node (ref "HDR1") (pin "45") (pinfunction "45_45") (pintype "passive"))
    )
    (net (code "99") (name "unconnected-(HDR1-Pad46)") (class "Default")
      (node (ref "HDR1") (pin "46") (pinfunction "46_46") (pintype "passive"))
    )
    (net (code "100") (name "unconnected-(HDR1-Pad47)") (class "Default")
      (node (ref "HDR1") (pin "47") (pinfunction "47_47") (pintype "passive"))
    )
    (net (code "101") (name "unconnected-(HDR1-Pad48)") (class "Default")
      (node (ref "HDR1") (pin "48") (pinfunction "48_48") (pintype "passive"))
    )
    (net (code "102") (name "unconnected-(HDR1-Pad49)") (class "Default")
      (node (ref "HDR1") (pin "49") (pinfunction "49_49") (pintype "passive"))
    )
    (net (code "103") (name "unconnected-(HDR1-Pad50)") (class "Default")
      (node (ref "HDR1") (pin "50") (pinfunction "50_50") (pintype "passive"))
    )
    (net (code "104") (name "unconnected-(HDR1-Pad51)") (class "Default")
      (node (ref "HDR1") (pin "51") (pinfunction "51_51") (pintype "passive"))
    )
    (net (code "105") (name "unconnected-(HDR1-Pad52)") (class "Default")
      (node (ref "HDR1") (pin "52") (pinfunction "52_52") (pintype "passive"))
    )
    (net (code "106") (name "unconnected-(HDR1-Pad53)") (class "Default")
      (node (ref "HDR1") (pin "53") (pinfunction "53_53") (pintype "passive"))
    )
    (net (code "107") (name "unconnected-(HDR1-Pad55)") (class "Default")
      (node (ref "HDR1") (pin "55") (pinfunction "55_55") (pintype "passive"))
    )
    (net (code "108") (name "unconnected-(HDR1-Pad56)") (class "Default")
      (node (ref "HDR1") (pin "56") (pinfunction "56_56") (pintype "passive"))
    )
    (net (code "109") (name "unconnected-(HDR1-Pad57)") (class "Default")
      (node (ref "HDR1") (pin "57") (pinfunction "57_57") (pintype "passive"))
    )
    (net (code "110") (name "unconnected-(HDR1-Pad58)") (class "Default")
      (node (ref "HDR1") (pin "58") (pinfunction "58_58") (pintype "passive"))
    )
    (net (code "111") (name "unconnected-(HDR1-Pad60)") (class "Default")
      (node (ref "HDR1") (pin "60") (pinfunction "60_60") (pintype "passive"))
    )
    (net (code "112") (name "unconnected-(HDR1-Pad62)") (class "Default")
      (node (ref "HDR1") (pin "62") (pinfunction "62_62") (pintype "passive"))
    )
    (net (code "113") (name "unconnected-(HDR1-Pad64)") (class "Default")
      (node (ref "HDR1") (pin "64") (pinfunction "64_64") (pintype "passive"))
    )
    (net (code "114") (name "unconnected-(HDR1-Pad66)") (class "Default")
      (node (ref "HDR1") (pin "66") (pinfunction "66_66") (pintype "passive"))
    )
    (net (code "115") (name "unconnected-(HDR1-Pad68)") (class "Default")
      (node (ref "HDR1") (pin "68") (pinfunction "68_68") (pintype "passive"))
    )
    (net (code "116") (name "unconnected-(HDR1-Pad76)") (class "Default")
      (node (ref "HDR1") (pin "76") (pinfunction "76_76") (pintype "passive"))
    )
    (net (code "117") (name "unconnected-(HDR1-Pad80)") (class "Default")
      (node (ref "HDR1") (pin "80") (pinfunction "80_80") (pintype "passive"))
    )
    (net (code "118") (name "unconnected-(HDR1-Pad82)") (class "Default")
      (node (ref "HDR1") (pin "82") (pinfunction "82_82") (pintype "passive"))
    )
    (net (code "119") (name "unconnected-(HDR1-Pad83)") (class "Default")
      (node (ref "HDR1") (pin "83") (pinfunction "83_83") (pintype "passive"))
    )
    (net (code "120") (name "unconnected-(HDR1-Pad84)") (class "Default")
      (node (ref "HDR1") (pin "84") (pinfunction "84_84") (pintype "passive"))
    )
    (net (code "121") (name "unconnected-(HDR1-Pad85)") (class "Default")
      (node (ref "HDR1") (pin "85") (pinfunction "85_85") (pintype "passive"))
    )
    (net (code "122") (name "unconnected-(HDR1-Pad86)") (class "Default")
      (node (ref "HDR1") (pin "86") (pinfunction "86_86") (pintype "passive"))
    )
    (net (code "123") (name "unconnected-(HDR1-Pad87)") (class "Default")
      (node (ref "HDR1") (pin "87") (pinfunction "87_87") (pintype "passive"))
    )
    (net (code "124") (name "unconnected-(HDR1-Pad88)") (class "Default")
      (node (ref "HDR1") (pin "88") (pinfunction "88_88") (pintype "passive"))
    )
    (net (code "125") (name "unconnected-(HDR1-Pad89)") (class "Default")
      (node (ref "HDR1") (pin "89") (pinfunction "89_89") (pintype "passive"))
    )
    (net (code "126") (name "unconnected-(HDR1-Pad90)") (class "Default")
      (node (ref "HDR1") (pin "90") (pinfunction "90_90") (pintype "passive"))
    )
    (net (code "127") (name "unconnected-(HDR1-Pad92)") (class "Default")
      (node (ref "HDR1") (pin "92") (pinfunction "92_92") (pintype "passive"))
    )
    (net (code "128") (name "unconnected-(HDR2-Pad3)") (class "Default")
      (node (ref "HDR2") (pin "3") (pinfunction "3_3") (pintype "passive"))
    )
    (net (code "129") (name "unconnected-(HDR2-Pad5)") (class "Default")
      (node (ref "HDR2") (pin "5") (pinfunction "5_5") (pintype "passive"))
    )
    (net (code "130") (name "unconnected-(HDR2-Pad43)") (class "Default")
      (node (ref "HDR2") (pin "43") (pinfunction "43_43") (pintype "passive"))
    )
    (net (code "131") (name "unconnected-(HDR2-Pad45)") (class "Default")
      (node (ref "HDR2") (pin "45") (pinfunction "45_45") (pintype "passive"))
    )
    (net (code "132") (name "unconnected-(HDR2-Pad47)") (class "Default")
      (node (ref "HDR2") (pin "47") (pinfunction "47_47") (pintype "passive"))
    )
    (net (code "133") (name "unconnected-(HDR2-Pad49)") (class "Default")
      (node (ref "HDR2") (pin "49") (pinfunction "49_49") (pintype "passive"))
    )
    (net (code "134") (name "unconnected-(HDR2-Pad51)") (class "Default")
      (node (ref "HDR2") (pin "51") (pinfunction "51_51") (pintype "passive"))
    )
    (net (code "135") (name "unconnected-(HDR2-Pad53)") (class "Default")
      (node (ref "HDR2") (pin "53") (pinfunction "53_53") (pintype "passive"))
    )
    (net (code "136") (name "unconnected-(HDR2-Pad55)") (class "Default")
      (node (ref "HDR2") (pin "55") (pinfunction "55_55") (pintype "passive"))
    )
    (net (code "137") (name "unconnected-(HDR2-Pad57)") (class "Default")
      (node (ref "HDR2") (pin "57") (pinfunction "57_57") (pintype "passive"))
    )
    (net (code "138") (name "unconnected-(HDR2-Pad59)") (class "Default")
      (node (ref "HDR2") (pin "59") (pinfunction "59_59") (pintype "passive"))
    )
    (net (code "139") (name "unconnected-(HDR2-Pad61)") (class "Default")
      (node (ref "HDR2") (pin "61") (pinfunction "61_61") (pintype "passive"))
    )
    (net (code "140") (name "unconnected-(HDR2-Pad63)") (class "Default")
      (node (ref "HDR2") (pin "63") (pinfunction "63_63") (pintype "passive"))
    )
    (net (code "141") (name "unconnected-(HDR2-Pad65)") (class "Default")
      (node (ref "HDR2") (pin "65") (pinfunction "65_65") (pintype "passive"))
    )
    (net (code "142") (name "unconnected-(HDR2-Pad67)") (class "Default")
      (node (ref "HDR2") (pin "67") (pinfunction "67_67") (pintype "passive"))
    )
    (net (code "143") (name "unconnected-(HDR2-Pad69)") (class "Default")
      (node (ref "HDR2") (pin "69") (pinfunction "69_69") (pintype "passive"))
    )
    (net (code "144") (name "unconnected-(HDR2-Pad71)") (class "Default")
      (node (ref "HDR2") (pin "71") (pinfunction "71_71") (pintype "passive"))
    )
    (net (code "145") (name "unconnected-(HDR2-Pad73)") (class "Default")
      (node (ref "HDR2") (pin "73") (pinfunction "73_73") (pintype "passive"))
    )
    (net (code "146") (name "unconnected-(HDR2-Pad75)") (class "Default")
      (node (ref "HDR2") (pin "75") (pinfunction "75_75") (pintype "passive"))
    )
    (net (code "147") (name "unconnected-(HDR2-Pad76)") (class "Default")
      (node (ref "HDR2") (pin "76") (pinfunction "76_76") (pintype "passive"))
    )
    (net (code "148") (name "unconnected-(HDR2-Pad77)") (class "Default")
      (node (ref "HDR2") (pin "77") (pinfunction "77_77") (pintype "passive"))
    )
    (net (code "149") (name "unconnected-(HDR2-Pad78)") (class "Default")
      (node (ref "HDR2") (pin "78") (pinfunction "78_78") (pintype "passive"))
    )
    (net (code "150") (name "unconnected-(HDR2-Pad79)") (class "Default")
      (node (ref "HDR2") (pin "79") (pinfunction "79_79") (pintype "passive"))
    )
    (net (code "151") (name "unconnected-(HDR2-Pad80)") (class "Default")
      (node (ref "HDR2") (pin "80") (pinfunction "80_80") (pintype "passive"))
    )
    (net (code "152") (name "unconnected-(HDR2-Pad81)") (class "Default")
      (node (ref "HDR2") (pin "81") (pinfunction "81_81") (pintype "passive"))
    )
    (net (code "153") (name "unconnected-(HDR2-Pad82)") (class "Default")
      (node (ref "HDR2") (pin "82") (pinfunction "82_82") (pintype "passive"))
    )
    (net (code "154") (name "unconnected-(HDR2-Pad83)") (class "Default")
      (node (ref "HDR2") (pin "83") (pinfunction "83_83") (pintype "passive"))
    )
    (net (code "155") (name "unconnected-(HDR2-Pad84)") (class "Default")
      (node (ref "HDR2") (pin "84") (pinfunction "84_84") (pintype "passive"))
    )
    (net (code "156") (name "unconnected-(HDR2-Pad85)") (class "Default")
      (node (ref "HDR2") (pin "85") (pinfunction "85_85") (pintype "passive"))
    )
    (net (code "157") (name "unconnected-(HDR2-Pad86)") (class "Default")
      (node (ref "HDR2") (pin "86") (pinfunction "86_86") (pintype "passive"))
    )
    (net (code "158") (name "unconnected-(HDR2-Pad87)") (class "Default")
      (node (ref "HDR2") (pin "87") (pinfunction "87_87") (pintype "passive"))
    )
    (net (code "159") (name "unconnected-(HDR2-Pad88)") (class "Default")
      (node (ref "HDR2") (pin "88") (pinfunction "88_88") (pintype "passive"))
    )
    (net (code "160") (name "unconnected-(HDR2-Pad89)") (class "Default")
      (node (ref "HDR2") (pin "89") (pinfunction "89_89") (pintype "passive"))
    )
    (net (code "161") (name "unconnected-(HDR2-Pad90)") (class "Default")
      (node (ref "HDR2") (pin "90") (pinfunction "90_90") (pintype "passive"))
    )
    (net (code "162") (name "unconnected-(HDR2-Pad91)") (class "Default")
      (node (ref "HDR2") (pin "91") (pinfunction "91_91") (pintype "passive"))
    )
    (net (code "163") (name "unconnected-(HDR2-Pad92)") (class "Default")
      (node (ref "HDR2") (pin "92") (pinfunction "92_92") (pintype "passive"))
    )
    (net (code "164") (name "unconnected-(U1-IO{slash}NC-Pad6)") (class "Default")
      (node (ref "U1") (pin "6") (pinfunction "IO/NC_6") (pintype "passive+no_connect"))
    )
    (net (code "165") (name "unconnected-(U1-IO{slash}NC-Pad39)") (class "Default")
      (node (ref "U1") (pin "39") (pinfunction "IO/NC_39") (pintype "passive+no_connect"))
    )
    (net (code "166") (name "unconnected-(U1-IO{slash}NC-Pad46)") (class "Default")
      (node (ref "U1") (pin "46") (pinfunction "IO/NC_46") (pintype "passive+no_connect"))
    )
    (net (code "167") (name "unconnected-(U1-IO{slash}NC-Pad79)") (class "Default")
      (node (ref "U1") (pin "79") (pinfunction "IO/NC_79") (pintype "passive+no_connect"))
    )
    (net (code "168") (name "unconnected-(U3-NC-Pad1)") (class "Default")
      (node (ref "U3") (pin "1") (pinfunction "NC_1") (pintype "passive"))
    )
  )
)
